# Power.net
KiCad netlist of a schematic drawn in Altium Designer
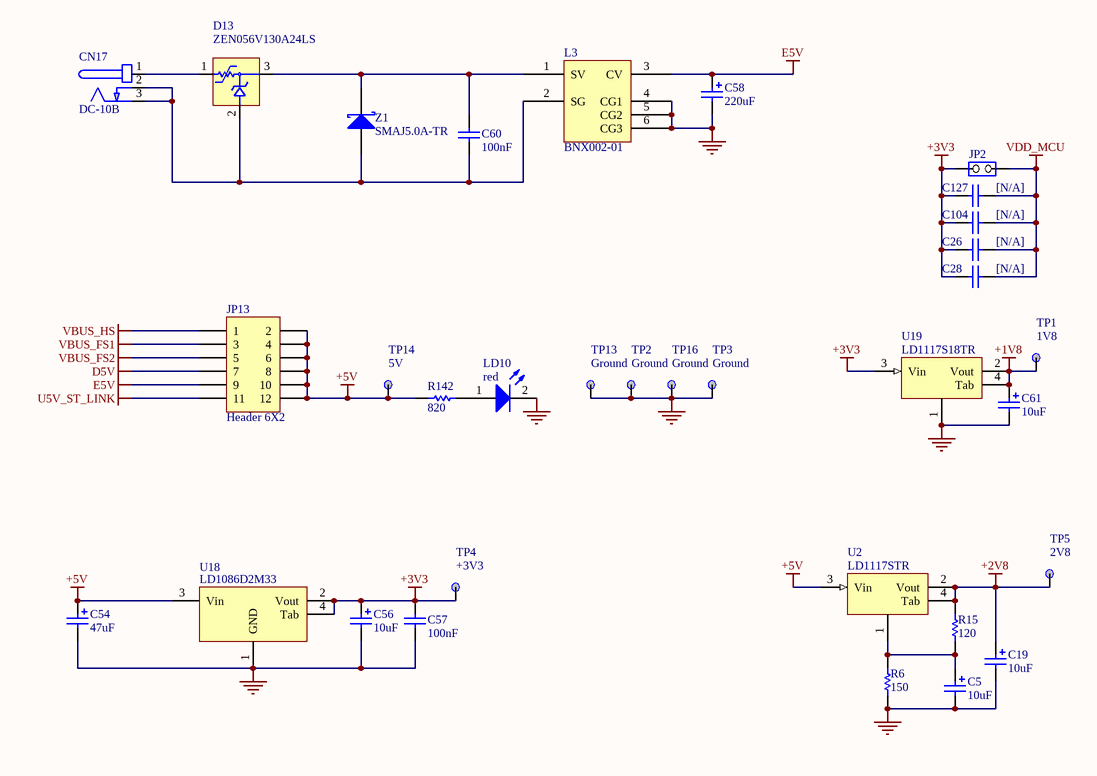
[diagram p0: Power.SchDoc]

(export (version "E")
  (design (tool "Eeschema 10.0.6"))
  (components
    (comp (ref "C5")
      (value "10uF")
      (footprint "TAN-A")
      (description "Polarized Capacitor (Radial)")
      (fields (field (name "PUBLISHER") "Altium Limited"))
      (libsource (lib "Miscellaneous Devices") (part "Cap Pol1"))
    )
    (comp (ref "C19")
      (value "10uF")
      (footprint "TAN-A")
      (description "Polarized Capacitor (Radial)")
      (fields (field (name "PUBLISHER") "Altium Limited"))
      (libsource (lib "Miscellaneous Devices") (part "Cap Pol1"))
    )
    (comp (ref "C26")
      (value "[N/A]")
      (footprint "0603C")
      (description "Capacitor")
      (fields (field (name "PUBLISHER") "Altium Limited"))
      (libsource (lib "Miscellaneous Devices") (part "Cap"))
    )
    (comp (ref "C28")
      (value "[N/A]")
      (footprint "0603C")
      (description "Capacitor")
      (fields (field (name "PUBLISHER") "Altium Limited"))
      (libsource (lib "Miscellaneous Devices") (part "Cap"))
    )
    (comp (ref "C54")
      (value "47uF")
      (footprint "CAE_5R3X5R3_H5R4")
      (description "Polarized Capacitor (Radial)")
      (fields (field (name "PUBLISHER") "Altium Limited"))
      (libsource (lib "Miscellaneous Devices") (part "Cap Pol1"))
    )
    (comp (ref "C56")
      (value "10uF")
      (footprint "TAN-A")
      (description "Polarized Capacitor (Radial)")
      (fields (field (name "PUBLISHER") "Altium Limited"))
      (libsource (lib "Miscellaneous Devices") (part "Cap Pol1"))
    )
    (comp (ref "C57")
      (value "100nF")
      (footprint "0603C")
      (description "Capacitor")
      (fields (field (name "PUBLISHER") "Altium Limited"))
      (libsource (lib "Miscellaneous Devices") (part "Cap"))
    )
    (comp (ref "C58")
      (value "220uF")
      (footprint "c310m-6")
      (description "Polarized Capacitor (Radial)")
      (fields (field (name "PUBLISHER") "Altium Limited"))
      (libsource (lib "Miscellaneous Devices") (part "Cap Pol1"))
    )
    (comp (ref "C60")
      (value "100nF")
      (footprint "0603C")
      (description "Capacitor")
      (fields (field (name "PUBLISHER") "Altium Limited"))
      (libsource (lib "Miscellaneous Devices") (part "CAP"))
    )
    (comp (ref "C61")
      (value "10uF")
      (footprint "TAN-A")
      (description "Polarized Capacitor (Radial)")
      (fields (field (name "PUBLISHER") "Altium Limited"))
      (libsource (lib "Miscellaneous Devices") (part "Cap Pol1"))
    )
    (comp (ref "C104")
      (value "[N/A]")
      (footprint "0603C")
      (description "Capacitor")
      (fields (field (name "PUBLISHER") "Altium Limited"))
      (libsource (lib "Miscellaneous Devices") (part "Cap"))
    )
    (comp (ref "C127")
      (value "[N/A]")
      (footprint "0603C")
      (description "Capacitor")
      (fields (field (name "PUBLISHER") "Altium Limited"))
      (libsource (lib "Miscellaneous Devices") (part "Cap"))
    )
    (comp (ref "CN17")
      (value "DC-10B")
      (footprint "PWR_JACK_DC10")
      (libsource (lib "STR910_SCHLIB") (part "PJ202A"))
    )
    (comp (ref "D13")
      (value "ZEN056V130A24LS")
      (footprint "TYCO_ZEN056V130A24LS")
      (libsource (lib "STR910_SCHLIB") (part "ZEN056V130A24LS"))
    )
    (comp (ref "JP2") (value "~") (footprint "SIP2") (libsource (lib "*") (part "JP2")))
    (comp (ref "JP13")
      (value "Header 6X2")
      (footprint "HDR_2X6_2R54")
      (description "Header, 6-Pin, Dual row")
      (fields (field (name "PUBLISHER") "Altium Limited"))
      (libsource (lib "mb1045") (part "Header 6X2"))
    )
    (comp (ref "L3")
      (value "BNX002-01")
      (footprint "BNX001")
      (libsource (lib "STR910_SCHLIB") (part "BNX002"))
    )
    (comp (ref "LD10")
      (value "red")
      (footprint "0603D")
      (description "Typical RED, GREEN, YELLOW, AMBER GaAs LED")
      (fields (field (name "PUBLISHER") "Altium Limited"))
      (libsource (lib "Miscellaneous Devices") (part "LED2"))
    )
    (comp (ref "R6")
      (value "150")
      (footprint "0603R")
      (description "Resistor")
      (fields (field (name "PUBLISHER") "Altium Limited"))
      (libsource (lib "Miscellaneous Devices") (part "res1"))
    )
    (comp (ref "R15")
      (value "120")
      (footprint "0603R")
      (description "Resistor")
      (fields (field (name "PUBLISHER") "Altium Limited"))
      (libsource (lib "Miscellaneous Devices") (part "res1"))
    )
    (comp (ref "R142")
      (value "820")
      (footprint "0603R")
      (description "Resistor")
      (fields (field (name "PUBLISHER") "Altium Limited"))
      (libsource (lib "Miscellaneous Devices") (part "res1"))
    )
    (comp (ref "TP1") (value "1V8") (footprint "TP") (libsource (lib "*") (part "TP")))
    (comp (ref "TP2") (value "Ground") (footprint "TP") (libsource (lib "*") (part "TP")))
    (comp (ref "TP3") (value "Ground") (footprint "TP") (libsource (lib "*") (part "TP")))
    (comp (ref "TP4") (value "+3V3") (footprint "TP") (libsource (lib "*") (part "TP")))
    (comp (ref "TP5") (value "2V8") (footprint "TP") (libsource (lib "*") (part "TP")))
    (comp (ref "TP13") (value "Ground") (footprint "TP") (libsource (lib "*") (part "TP")))
    (comp (ref "TP14") (value "5V") (footprint "TP") (libsource (lib "*") (part "TP")))
    (comp (ref "TP16") (value "Ground") (footprint "TP") (libsource (lib "*") (part "TP")))
    (comp (ref "U2") (value "LD1117STR") (footprint "SOT-223") (libsource (lib "mb1045") (part "LD1117")))
    (comp (ref "U18")
      (value "LD1086D2M33")
      (footprint "TO263-3")
      (libsource (lib "mb1045") (part "VOLTREG1"))
    )
    (comp (ref "U19") (value "LD1117S18TR") (footprint "SOT-223") (libsource (lib "mb1045") (part "LD1117")))
    (comp (ref "Z1")
      (value "SMAJ5.0A-TR")
      (footprint "sma")
      (description "Schottky Diode")
      (fields (field (name "PUBLISHER") "Altium Limited"))
      (libsource (lib "Miscellaneous Devices") (part "D Schottky"))
    )
  )
  (nets
    (net (code "1") (name "+1V8") (class "Default")
      (node (ref "C61") (pin "1") (pinfunction "1_1") (pintype "passive"))
      (node (ref "TP1") (pin "1") (pinfunction "1_1") (pintype "passive"))
      (node (ref "U19") (pin "2") (pinfunction "Vout_2") (pintype "power_in"))
      (node (ref "U19") (pin "4") (pinfunction "Tab_4") (pintype "power_in"))
    )
    (net (code "2") (name "+2V8") (class "Default")
      (node (ref "C19") (pin "1") (pinfunction "1_1") (pintype "passive"))
      (node (ref "R15") (pin "1") (pinfunction "1_1") (pintype "passive"))
      (node (ref "TP5") (pin "1") (pinfunction "1_1") (pintype "passive"))
      (node (ref "U2") (pin "2") (pinfunction "Vout_2") (pintype "power_in"))
      (node (ref "U2") (pin "4") (pinfunction "Tab_4") (pintype "power_in"))
    )
    (net (code "3") (name "+3V3") (class "Default")
      (node (ref "C104") (pin "1") (pinfunction "1_1") (pintype "passive"))
      (node (ref "C127") (pin "1") (pinfunction "1_1") (pintype "passive"))
      (node (ref "C26") (pin "1") (pinfunction "1_1") (pintype "passive"))
      (node (ref "C28") (pin "1") (pinfunction "1_1") (pintype "passive"))
      (node (ref "C56") (pin "1") (pinfunction "1_1") (pintype "passive"))
      (node (ref "C57") (pin "1") (pinfunction "1_1") (pintype "passive"))
      (node (ref "JP2") (pin "1") (pinfunction "COMMON_1") (pintype "passive"))
      (node (ref "TP4") (pin "1") (pinfunction "1_1") (pintype "passive"))
      (node (ref "U18") (pin "2") (pinfunction "Vout_2") (pintype "passive"))
      (node (ref "U18") (pin "4") (pinfunction "Tab_4") (pintype "passive"))
      (node (ref "U19") (pin "3") (pinfunction "Vin_3") (pintype "input"))
    )
    (net (code "4") (name "+5V") (class "Default")
      (node (ref "C54") (pin "1") (pinfunction "1_1") (pintype "passive"))
      (node (ref "JP13") (pin "10") (pinfunction "10_10") (pintype "passive"))
      (node (ref "JP13") (pin "12") (pinfunction "12_12") (pintype "passive"))
      (node (ref "JP13") (pin "2") (pinfunction "2_2") (pintype "passive"))
      (node (ref "JP13") (pin "4") (pinfunction "4_4") (pintype "passive"))
      (node (ref "JP13") (pin "6") (pinfunction "6_6") (pintype "passive"))
      (node (ref "JP13") (pin "8") (pinfunction "8_8") (pintype "passive"))
      (node (ref "R142") (pin "2") (pinfunction "2_2") (pintype "passive"))
      (node (ref "TP14") (pin "1") (pinfunction "1_1") (pintype "passive"))
      (node (ref "U18") (pin "3") (pinfunction "Vin_3") (pintype "passive"))
      (node (ref "U2") (pin "3") (pinfunction "Vin_3") (pintype "input"))
    )
    (net (code "5") (name "D5V") (class "Default")
      (node (ref "JP13") (pin "7") (pinfunction "7_7") (pintype "passive"))
    )
    (net (code "6") (name "E5V") (class "Default")
      (node (ref "C58") (pin "1") (pinfunction "1_1") (pintype "passive"))
      (node (ref "JP13") (pin "9") (pinfunction "9_9") (pintype "passive"))
      (node (ref "L3") (pin "3") (pinfunction "CV_3") (pintype "passive"))
    )
    (net (code "7") (name "GND") (class "Default")
      (node (ref "C19") (pin "2") (pinfunction "2_2") (pintype "passive"))
      (node (ref "C5") (pin "2") (pinfunction "2_2") (pintype "passive"))
      (node (ref "C54") (pin "2") (pinfunction "2_2") (pintype "passive"))
      (node (ref "C56") (pin "2") (pinfunction "2_2") (pintype "passive"))
      (node (ref "C57") (pin "2") (pinfunction "2_2") (pintype "passive"))
      (node (ref "C58") (pin "2") (pinfunction "2_2") (pintype "passive"))
      (node (ref "C61") (pin "2") (pinfunction "2_2") (pintype "passive"))
      (node (ref "L3") (pin "4") (pinfunction "CG1_4") (pintype "passive"))
      (node (ref "L3") (pin "5") (pinfunction "CG2_5") (pintype "passive"))
      (node (ref "L3") (pin "6") (pinfunction "CG3_6") (pintype "passive"))
      (node (ref "LD10") (pin "2") (pinfunction "K_2") (pintype "passive"))
      (node (ref "R6") (pin "2") (pinfunction "2_2") (pintype "passive"))
      (node (ref "TP13") (pin "1") (pinfunction "1_1") (pintype "passive"))
      (node (ref "TP16") (pin "1") (pinfunction "1_1") (pintype "passive"))
      (node (ref "TP2") (pin "1") (pinfunction "1_1") (pintype "passive"))
      (node (ref "TP3") (pin "1") (pinfunction "1_1") (pintype "passive"))
      (node (ref "U18") (pin "1") (pinfunction "GND_1") (pintype "passive"))
      (node (ref "U19") (pin "1") (pintype "passive"))
    )
    (net (code "8") (name "Net-(C5-Pad1)") (class "Default")
      (node (ref "C5") (pin "1") (pinfunction "1_1") (pintype "passive"))
      (node (ref "R15") (pin "2") (pinfunction "2_2") (pintype "passive"))
      (node (ref "R6") (pin "1") (pinfunction "1_1") (pintype "passive"))
      (node (ref "U2") (pin "1") (pintype "passive"))
    )
    (net (code "9") (name "Net-(CN17-+)") (class "Default")
      (node (ref "CN17") (pin "1") (pinfunction "+_1") (pintype "passive"))
      (node (ref "D13") (pin "1") (pintype "passive"))
    )
    (net (code "10") (name "Net-(L3-SG)") (class "Default")
      (node (ref "C60") (pin "2") (pinfunction "2_2") (pintype "passive"))
      (node (ref "CN17") (pin "2") (pinfunction "GND_2") (pintype "passive"))
      (node (ref "CN17") (pin "3") (pinfunction "GND_3") (pintype "passive"))
      (node (ref "D13") (pin "2") (pintype "passive"))
      (node (ref "L3") (pin "2") (pinfunction "SG_2") (pintype "passive"))
      (node (ref "Z1") (pin "1") (pinfunction "A_1") (pintype "passive"))
    )
    (net (code "11") (name "Net-(L3-SV)") (class "Default")
      (node (ref "C60") (pin "1") (pinfunction "1_1") (pintype "passive"))
      (node (ref "D13") (pin "3") (pintype "passive"))
      (node (ref "L3") (pin "1") (pinfunction "SV_1") (pintype "passive"))
      (node (ref "Z1") (pin "2") (pinfunction "K_2") (pintype "passive"))
    )
    (net (code "12") (name "Net-(LD10-A)") (class "Default")
      (node (ref "LD10") (pin "1") (pinfunction "A_1") (pintype "passive"))
      (node (ref "R142") (pin "1") (pinfunction "1_1") (pintype "passive"))
    )
    (net (code "13") (name "U5V_ST_LINK") (class "Default")
      (node (ref "JP13") (pin "11") (pinfunction "11_11") (pintype "passive"))
    )
    (net (code "14") (name "VBUS_FS1") (class "Default")
      (node (ref "JP13") (pin "3") (pinfunction "3_3") (pintype "passive"))
    )
    (net (code "15") (name "VBUS_FS2") (class "Default")
      (node (ref "JP13") (pin "5") (pinfunction "5_5") (pintype "passive"))
    )
    (net (code "16") (name "VBUS_HS") (class "Default")
      (node (ref "JP13") (pin "1") (pinfunction "1_1") (pintype "passive"))
    )
    (net (code "17") (name "VDD_MCU") (class "Default")
      (node (ref "C104") (pin "2") (pinfunction "2_2") (pintype "passive"))
      (node (ref "C127") (pin "2") (pinfunction "2_2") (pintype "passive"))
      (node (ref "C26") (pin "2") (pinfunction "2_2") (pintype "passive"))
      (node (ref "C28") (pin "2") (pinfunction "2_2") (pintype "passive"))
      (node (ref "JP2") (pin "2") (pinfunction "NO_2") (pintype "passive"))
    )
  )
)
